# motherboard_v1_20.net
KiCad netlist of a schematic drawn in EAGLE
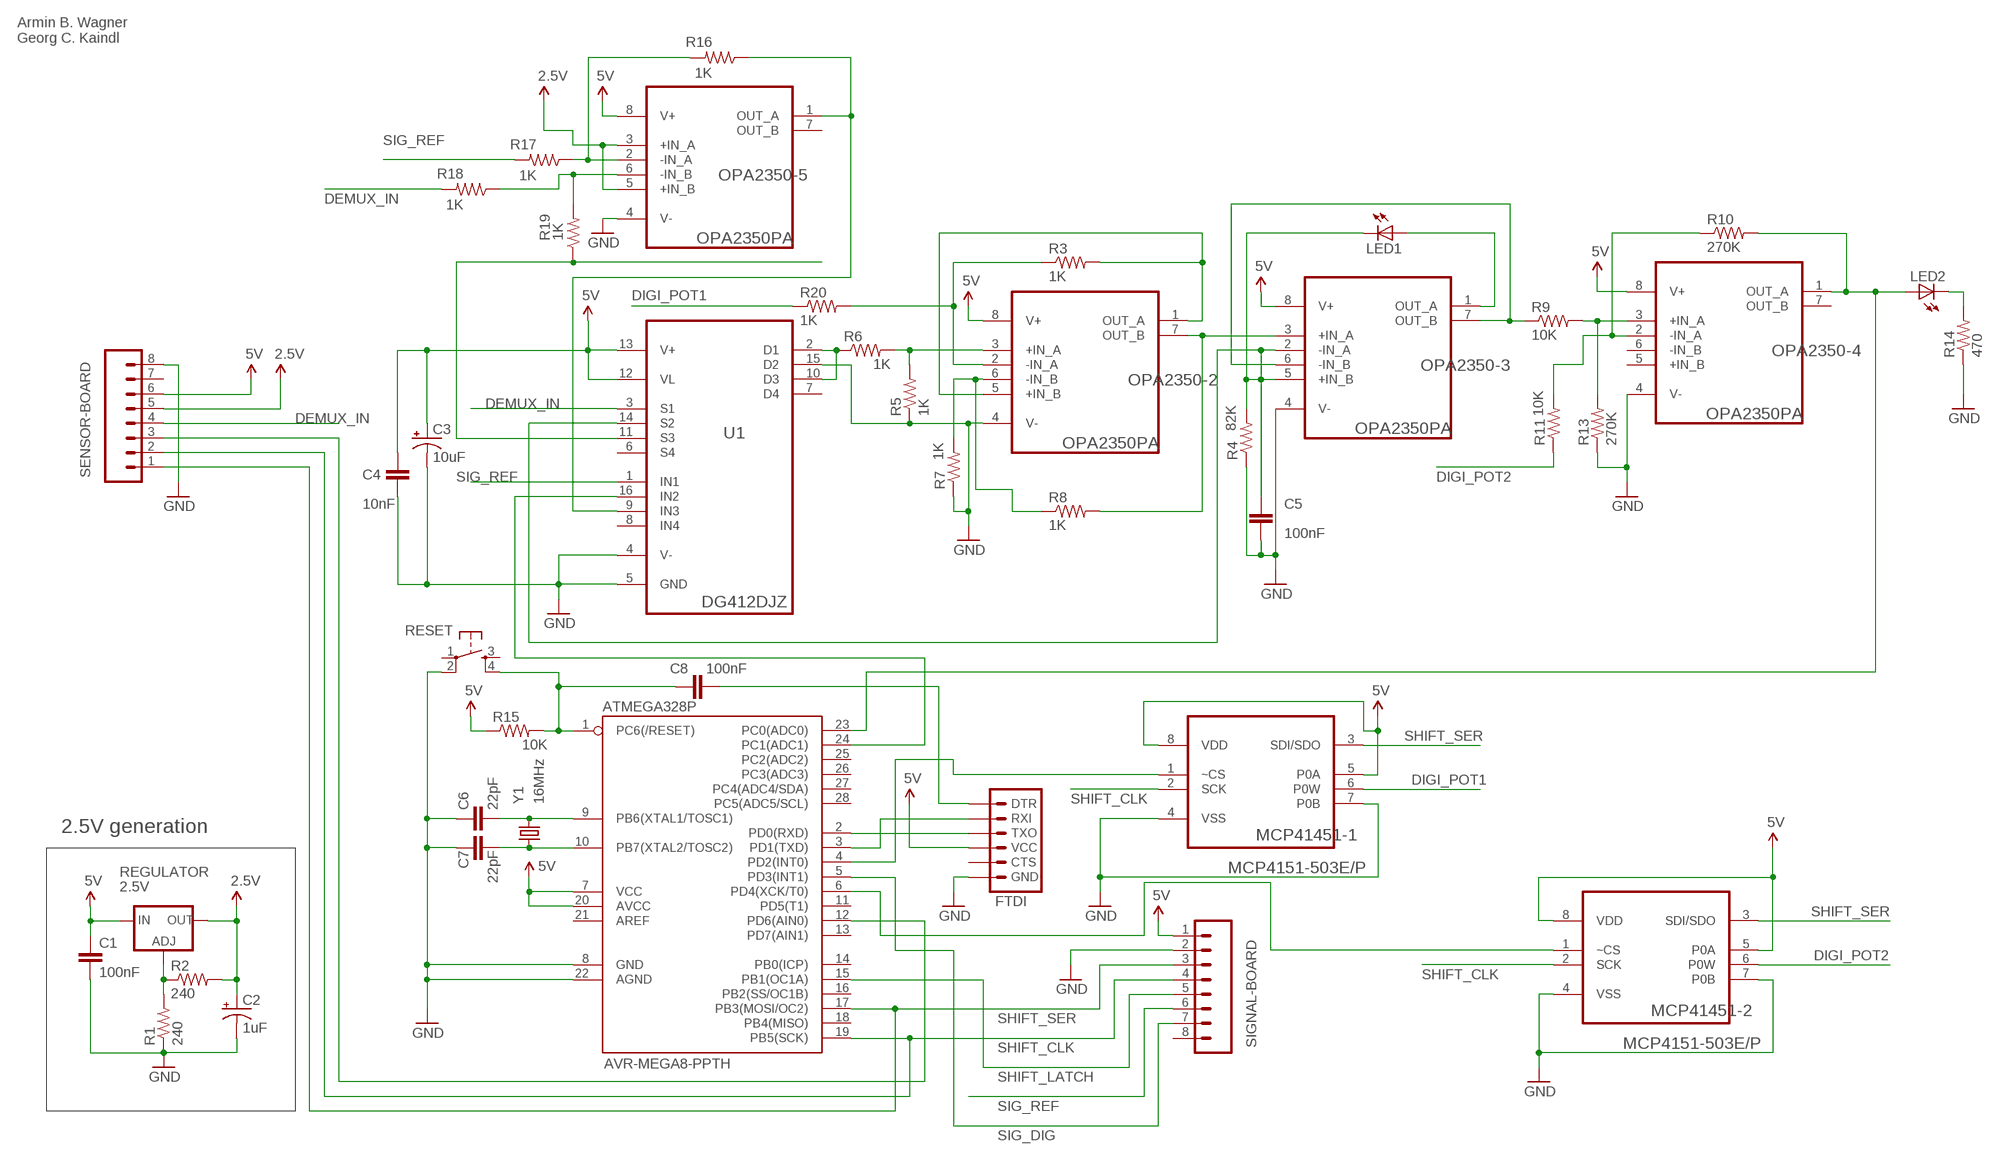
[diagram p0: schematic, sheet 1]

(export (version "E")
  (design (tool "Eeschema 10.0.6"))
  (components
    (comp (ref "ATMEGA328P")
      (value "AVR-MEGA8-PPTH")
      (footprint "eagle-import:DIL28-3")
      (libsource (lib "eagle-import") (part "AVR-MEGA8-PPTH"))
    )
    (comp (ref "C1")
      (value "100nF")
      (footprint "eagle-import:CAP-PTH-SMALL")
      (libsource (lib "eagle-import") (part "CAPPTH"))
    )
    (comp (ref "C2")
      (value "1uF")
      (footprint "eagle-import:CPOL-RADIAL-10UF-25V")
      (libsource (lib "eagle-import") (part "CAP_POLPTH2"))
    )
    (comp (ref "C3")
      (value "10uF")
      (footprint "eagle-import:CPOL-RADIAL-10UF-25V")
      (libsource (lib "eagle-import") (part "CAP_POLPTH2"))
    )
    (comp (ref "C4")
      (value "10nF")
      (footprint "eagle-import:CAP-PTH-SMALL")
      (libsource (lib "eagle-import") (part "CAPPTH"))
    )
    (comp (ref "C5")
      (value "100nF")
      (footprint "eagle-import:CAP-PTH-SMALL")
      (libsource (lib "eagle-import") (part "CAPPTH"))
    )
    (comp (ref "C6")
      (value "22pF")
      (footprint "eagle-import:CAP-PTH-SMALL2")
      (libsource (lib "eagle-import") (part "CAPPTH2"))
    )
    (comp (ref "C7")
      (value "22pF")
      (footprint "eagle-import:CAP-PTH-SMALL2")
      (libsource (lib "eagle-import") (part "CAPPTH2"))
    )
    (comp (ref "C8")
      (value "100nF")
      (footprint "eagle-import:CAP-PTH-SMALL2")
      (libsource (lib "eagle-import") (part "CAPPTH2"))
    )
    (comp (ref "FTDI")
      (value "ARDUINO_SERIAL_PROGRAMLONGPADS")
      (footprint "eagle-import:1X06_LONGPADS")
      (libsource (lib "eagle-import") (part "ARDUINO_SERIAL_PROGRAMLONGPADS"))
    )
    (comp (ref "LED1")
      (value "LED3MM")
      (footprint "eagle-import:LED3MM")
      (libsource (lib "eagle-import") (part "LED3MM"))
    )
    (comp (ref "LED2")
      (value "LED5MM")
      (footprint "eagle-import:LED5MM")
      (libsource (lib "eagle-import") (part "LED5MM"))
    )
    (comp (ref "MCP41451-1")
      (value "MCP4151-503E/P")
      (footprint "eagle-import:DIP254P762X533-8")
      (libsource (lib "eagle-import") (part "MCP4151-503E/P"))
    )
    (comp (ref "MCP41451-2")
      (value "MCP4151-503E/P")
      (footprint "eagle-import:DIP254P762X533-8")
      (libsource (lib "eagle-import") (part "MCP4151-503E/P"))
    )
    (comp (ref "OPA2350-2")
      (value "OPA2350PA")
      (footprint "eagle-import:DIP254P762X508-8")
      (libsource (lib "eagle-import") (part "OPA2350PA"))
    )
    (comp (ref "OPA2350-3")
      (value "OPA2350PA")
      (footprint "eagle-import:DIP254P762X508-8")
      (libsource (lib "eagle-import") (part "OPA2350PA"))
    )
    (comp (ref "OPA2350-4")
      (value "OPA2350PA")
      (footprint "eagle-import:DIP254P762X508-8")
      (libsource (lib "eagle-import") (part "OPA2350PA"))
    )
    (comp (ref "OPA2350-5")
      (value "OPA2350PA")
      (footprint "eagle-import:DIP254P762X508-8")
      (libsource (lib "eagle-import") (part "OPA2350PA"))
    )
    (comp (ref "R1")
      (value "240")
      (footprint "eagle-import:AXIAL-0.3")
      (libsource (lib "eagle-import") (part "RESISTORAXIAL-0.3"))
    )
    (comp (ref "R2")
      (value "240")
      (footprint "eagle-import:AXIAL-0.3")
      (libsource (lib "eagle-import") (part "RESISTORAXIAL-0.3"))
    )
    (comp (ref "R3")
      (value "1K")
      (footprint "eagle-import:AXIAL-0.3")
      (libsource (lib "eagle-import") (part "RESISTORAXIAL-0.3"))
    )
    (comp (ref "R4")
      (value "82K")
      (footprint "eagle-import:AXIAL-0.3")
      (libsource (lib "eagle-import") (part "RESISTORAXIAL-0.3"))
    )
    (comp (ref "R5")
      (value "1K")
      (footprint "eagle-import:AXIAL-0.3")
      (libsource (lib "eagle-import") (part "RESISTORAXIAL-0.3"))
    )
    (comp (ref "R6")
      (value "1K")
      (footprint "eagle-import:AXIAL-0.3")
      (libsource (lib "eagle-import") (part "RESISTORAXIAL-0.3"))
    )
    (comp (ref "R7")
      (value "1K")
      (footprint "eagle-import:AXIAL-0.3")
      (libsource (lib "eagle-import") (part "RESISTORAXIAL-0.3"))
    )
    (comp (ref "R8")
      (value "1K")
      (footprint "eagle-import:AXIAL-0.3")
      (libsource (lib "eagle-import") (part "RESISTORAXIAL-0.3"))
    )
    (comp (ref "R9")
      (value "10K")
      (footprint "eagle-import:AXIAL-0.3")
      (libsource (lib "eagle-import") (part "RESISTORAXIAL-0.3"))
    )
    (comp (ref "R10")
      (value "270K")
      (footprint "eagle-import:AXIAL-0.3")
      (libsource (lib "eagle-import") (part "RESISTORAXIAL-0.3"))
    )
    (comp (ref "R11")
      (value "10K")
      (footprint "eagle-import:AXIAL-0.3")
      (libsource (lib "eagle-import") (part "RESISTORAXIAL-0.3"))
    )
    (comp (ref "R13")
      (value "270K")
      (footprint "eagle-import:AXIAL-0.3")
      (libsource (lib "eagle-import") (part "RESISTORAXIAL-0.3"))
    )
    (comp (ref "R14")
      (value "470")
      (footprint "eagle-import:AXIAL-0.3")
      (libsource (lib "eagle-import") (part "RESISTORAXIAL-0.3"))
    )
    (comp (ref "R15")
      (value "10K")
      (footprint "eagle-import:AXIAL-0.3")
      (libsource (lib "eagle-import") (part "RESISTORAXIAL-0.3"))
    )
    (comp (ref "R16")
      (value "1K")
      (footprint "eagle-import:AXIAL-0.3")
      (libsource (lib "eagle-import") (part "RESISTORAXIAL-0.3"))
    )
    (comp (ref "R17")
      (value "1K")
      (footprint "eagle-import:AXIAL-0.3")
      (libsource (lib "eagle-import") (part "RESISTORAXIAL-0.3"))
    )
    (comp (ref "R18")
      (value "1K")
      (footprint "eagle-import:AXIAL-0.3")
      (libsource (lib "eagle-import") (part "RESISTORAXIAL-0.3"))
    )
    (comp (ref "R19")
      (value "1K")
      (footprint "eagle-import:AXIAL-0.3")
      (libsource (lib "eagle-import") (part "RESISTORAXIAL-0.3"))
    )
    (comp (ref "R20")
      (value "1K")
      (footprint "eagle-import:AXIAL-0.3")
      (libsource (lib "eagle-import") (part "RESISTORAXIAL-0.3"))
    )
    (comp (ref "REGULATOR")
      (value "2.5V")
      (footprint "eagle-import:TO220-ADJ")
      (libsource (lib "eagle-import") (part "V_REG_317SINK"))
    )
    (comp (ref "RESET")
      (value "TAC_SWITCHPTH")
      (footprint "eagle-import:TACTILE-PTH")
      (libsource (lib "eagle-import") (part "TAC_SWITCHPTH"))
    )
    (comp (ref "SENSOR-BOARD")
      (value "M08LONGPADS")
      (footprint "eagle-import:1X08_LONGPADS")
      (libsource (lib "eagle-import") (part "M08LONGPADS"))
    )
    (comp (ref "SIGNAL-BOARD")
      (value "M08LONGPADS")
      (footprint "eagle-import:1X08_LONGPADS")
      (libsource (lib "eagle-import") (part "M08LONGPADS"))
    )
    (comp (ref "U1")
      (value "DG412DJZ")
      (footprint "eagle-import:DIP254P762X533-16")
      (libsource (lib "eagle-import") (part "DG412DJZ"))
    )
    (comp (ref "Y1")
      (value "16MHz")
      (footprint "eagle-import:HC49US")
      (libsource (lib "eagle-import") (part "CRYSTALHC49US"))
    )
  )
  (nets
    (net (code "1") (name "/DEMUX_IN") (class "Default")
      (node (ref "R18") (pin "P$2") (pinfunction "2_P$2") (pintype "passive"))
      (node (ref "SENSOR-BOARD") (pin "4") (pinfunction "4_4") (pintype "passive"))
      (node (ref "U1") (pin "3") (pinfunction "S1_3") (pintype "input"))
    )
    (net (code "2") (name "/DIGI_POT1") (class "Default")
      (node (ref "MCP41451-1") (pin "6") (pinfunction "P0W_6") (pintype "passive"))
      (node (ref "R20") (pin "P$1") (pinfunction "1_P$1") (pintype "passive"))
    )
    (net (code "3") (name "/DIGI_POT2") (class "Default")
      (node (ref "MCP41451-2") (pin "6") (pinfunction "P0W_6") (pintype "passive"))
      (node (ref "R11") (pin "P$1") (pinfunction "1_P$1") (pintype "passive"))
    )
    (net (code "4") (name "/SHIFT_CLK") (class "Default")
      (node (ref "ATMEGA328P") (pin "19") (pinfunction "PB5(SCK)_19") (pintype "bidirectional"))
      (node (ref "MCP41451-1") (pin "2") (pinfunction "SCK_2") (pintype "input"))
      (node (ref "MCP41451-2") (pin "2") (pinfunction "SCK_2") (pintype "input"))
      (node (ref "SENSOR-BOARD") (pin "2") (pinfunction "2_2") (pintype "passive"))
      (node (ref "SIGNAL-BOARD") (pin "4") (pinfunction "4_4") (pintype "passive"))
    )
    (net (code "5") (name "/SHIFT_LATCH") (class "Default")
      (node (ref "ATMEGA328P") (pin "15") (pinfunction "PB1(OC1A)_15") (pintype "bidirectional"))
      (node (ref "SIGNAL-BOARD") (pin "5") (pinfunction "5_5") (pintype "passive"))
    )
    (net (code "6") (name "/SHIFT_SER") (class "Default")
      (node (ref "ATMEGA328P") (pin "17") (pinfunction "PB3(MOSI/OC2)_17") (pintype "bidirectional"))
      (node (ref "MCP41451-1") (pin "3") (pinfunction "SDI/SDO_3") (pintype "bidirectional"))
      (node (ref "MCP41451-2") (pin "3") (pinfunction "SDI/SDO_3") (pintype "bidirectional"))
      (node (ref "SENSOR-BOARD") (pin "1") (pinfunction "1_1") (pintype "passive"))
      (node (ref "SIGNAL-BOARD") (pin "3") (pinfunction "3_3") (pintype "passive"))
    )
    (net (code "7") (name "/SIG_DIG") (class "Default")
      (node (ref "ATMEGA328P") (pin "5") (pinfunction "PD3(INT1)_5") (pintype "bidirectional"))
      (node (ref "SIGNAL-BOARD") (pin "7") (pinfunction "7_7") (pintype "passive"))
    )
    (net (code "8") (name "/SIG_REF") (class "Default")
      (node (ref "R17") (pin "P$2") (pinfunction "2_P$2") (pintype "passive"))
      (node (ref "SIGNAL-BOARD") (pin "6") (pinfunction "6_6") (pintype "passive"))
      (node (ref "U1") (pin "1") (pinfunction "IN1_1") (pintype "input"))
    )
    (net (code "9") (name "2.5V") (class "Default")
      (node (ref "C2") (pin "1") (pinfunction "+_1") (pintype "passive"))
      (node (ref "OPA2350-5") (pin "3") (pinfunction "+IN_A_3") (pintype "input"))
      (node (ref "OPA2350-5") (pin "5") (pinfunction "+IN_B_5") (pintype "input"))
      (node (ref "R2") (pin "P$2") (pinfunction "2_P$2") (pintype "passive"))
      (node (ref "REGULATOR") (pin "OUT") (pinfunction "OUT_OUT") (pintype "output"))
      (node (ref "SENSOR-BOARD") (pin "5") (pinfunction "5_5") (pintype "passive"))
    )
    (net (code "10") (name "5V") (class "Default")
      (node (ref "ATMEGA328P") (pin "20") (pinfunction "AVCC_20") (pintype "bidirectional"))
      (node (ref "ATMEGA328P") (pin "7") (pinfunction "VCC_7") (pintype "bidirectional"))
      (node (ref "C1") (pin "1") (pinfunction "1_1") (pintype "passive"))
      (node (ref "C3") (pin "1") (pinfunction "+_1") (pintype "passive"))
      (node (ref "C4") (pin "1") (pinfunction "1_1") (pintype "passive"))
      (node (ref "FTDI") (pin "4") (pinfunction "VCC_4") (pintype "passive"))
      (node (ref "MCP41451-1") (pin "5") (pinfunction "P0A_5") (pintype "passive"))
      (node (ref "MCP41451-1") (pin "8") (pinfunction "VDD_8") (pintype "power_in"))
      (node (ref "MCP41451-2") (pin "5") (pinfunction "P0A_5") (pintype "passive"))
      (node (ref "MCP41451-2") (pin "8") (pinfunction "VDD_8") (pintype "power_in"))
      (node (ref "OPA2350-2") (pin "8") (pinfunction "V+_8") (pintype "power_in"))
      (node (ref "OPA2350-3") (pin "8") (pinfunction "V+_8") (pintype "power_in"))
      (node (ref "OPA2350-4") (pin "8") (pinfunction "V+_8") (pintype "power_in"))
      (node (ref "OPA2350-5") (pin "8") (pinfunction "V+_8") (pintype "power_in"))
      (node (ref "R15") (pin "P$1") (pinfunction "1_P$1") (pintype "passive"))
      (node (ref "REGULATOR") (pin "IN") (pinfunction "IN_IN") (pintype "input"))
      (node (ref "SENSOR-BOARD") (pin "6") (pinfunction "6_6") (pintype "passive"))
      (node (ref "SIGNAL-BOARD") (pin "1") (pinfunction "1_1") (pintype "passive"))
      (node (ref "U1") (pin "12") (pinfunction "VL_12") (pintype "power_in"))
      (node (ref "U1") (pin "13") (pinfunction "V+_13") (pintype "power_in"))
    )
    (net (code "11") (name "GND") (class "Default")
      (node (ref "ATMEGA328P") (pin "22") (pinfunction "AGND_22") (pintype "bidirectional"))
      (node (ref "ATMEGA328P") (pin "8") (pinfunction "GND_8") (pintype "bidirectional"))
      (node (ref "C1") (pin "2") (pinfunction "2_2") (pintype "passive"))
      (node (ref "C2") (pin "2") (pinfunction "-_2") (pintype "passive"))
      (node (ref "C3") (pin "2") (pinfunction "-_2") (pintype "passive"))
      (node (ref "C4") (pin "2") (pinfunction "2_2") (pintype "passive"))
      (node (ref "C5") (pin "2") (pinfunction "2_2") (pintype "passive"))
      (node (ref "C6") (pin "1") (pinfunction "1_1") (pintype "passive"))
      (node (ref "C7") (pin "1") (pinfunction "1_1") (pintype "passive"))
      (node (ref "FTDI") (pin "6") (pinfunction "GND_6") (pintype "passive"))
      (node (ref "MCP41451-1") (pin "4") (pinfunction "VSS_4") (pintype "power_in"))
      (node (ref "MCP41451-1") (pin "7") (pinfunction "P0B_7") (pintype "passive"))
      (node (ref "MCP41451-2") (pin "4") (pinfunction "VSS_4") (pintype "power_in"))
      (node (ref "MCP41451-2") (pin "7") (pinfunction "P0B_7") (pintype "passive"))
      (node (ref "OPA2350-2") (pin "4") (pinfunction "V-_4") (pintype "power_in"))
      (node (ref "OPA2350-3") (pin "4") (pinfunction "V-_4") (pintype "power_in"))
      (node (ref "OPA2350-4") (pin "4") (pinfunction "V-_4") (pintype "power_in"))
      (node (ref "OPA2350-5") (pin "4") (pinfunction "V-_4") (pintype "power_in"))
      (node (ref "R1") (pin "P$1") (pinfunction "1_P$1") (pintype "passive"))
      (node (ref "R13") (pin "P$1") (pinfunction "1_P$1") (pintype "passive"))
      (node (ref "R14") (pin "P$1") (pinfunction "1_P$1") (pintype "passive"))
      (node (ref "R4") (pin "P$1") (pinfunction "1_P$1") (pintype "passive"))
      (node (ref "R5") (pin "P$1") (pinfunction "1_P$1") (pintype "passive"))
      (node (ref "R7") (pin "P$1") (pinfunction "1_P$1") (pintype "passive"))
      (node (ref "RESET") (pin "2") (pinfunction "2_2") (pintype "passive"))
      (node (ref "SENSOR-BOARD") (pin "8") (pinfunction "8_8") (pintype "passive"))
      (node (ref "SIGNAL-BOARD") (pin "2") (pinfunction "2_2") (pintype "passive"))
      (node (ref "U1") (pin "15") (pinfunction "D2_15") (pintype "output"))
      (node (ref "U1") (pin "4") (pinfunction "V-_4") (pintype "power_in"))
      (node (ref "U1") (pin "5") (pinfunction "GND_5") (pintype "passive"))
    )
    (net (code "12") (name "Net-(ATMEGA328P-PB6(XTAL1{slash}TOSC1))") (class "Default")
      (node (ref "ATMEGA328P") (pin "9") (pinfunction "PB6(XTAL1/TOSC1)_9") (pintype "bidirectional"))
      (node (ref "C6") (pin "2") (pinfunction "2_2") (pintype "passive"))
      (node (ref "Y1") (pin "2") (pinfunction "2_2") (pintype "passive"))
    )
    (net (code "13") (name "Net-(ATMEGA328P-PB7(XTAL2{slash}TOSC2))") (class "Default")
      (node (ref "ATMEGA328P") (pin "10") (pinfunction "PB7(XTAL2/TOSC2)_10") (pintype "bidirectional"))
      (node (ref "C7") (pin "2") (pinfunction "2_2") (pintype "passive"))
      (node (ref "Y1") (pin "1") (pinfunction "1_1") (pintype "passive"))
    )
    (net (code "14") (name "Net-(ATMEGA328P-PC0(ADC0))") (class "Default")
      (node (ref "ATMEGA328P") (pin "23") (pinfunction "PC0(ADC0)_23") (pintype "bidirectional"))
      (node (ref "LED2") (pin "A") (pinfunction "A_A") (pintype "passive"))
      (node (ref "OPA2350-4") (pin "1") (pinfunction "OUT_A_1") (pintype "output"))
      (node (ref "R10") (pin "P$2") (pinfunction "2_P$2") (pintype "passive"))
    )
    (net (code "15") (name "Net-(ATMEGA328P-PC1(ADC1))") (class "Default")
      (node (ref "ATMEGA328P") (pin "24") (pinfunction "PC1(ADC1)_24") (pintype "bidirectional"))
      (node (ref "U1") (pin "16") (pinfunction "IN2_16") (pintype "input"))
    )
    (net (code "16") (name "Net-(ATMEGA328P-PC6({slash}RESET))") (class "Default")
      (node (ref "ATMEGA328P") (pin "1") (pinfunction "PC6(/RESET)_1") (pintype "bidirectional"))
      (node (ref "C8") (pin "1") (pinfunction "1_1") (pintype "passive"))
      (node (ref "R15") (pin "P$2") (pinfunction "2_P$2") (pintype "passive"))
      (node (ref "RESET") (pin "4") (pinfunction "4_4") (pintype "passive"))
    )
    (net (code "17") (name "Net-(ATMEGA328P-PD0(RXD))") (class "Default")
      (node (ref "ATMEGA328P") (pin "2") (pinfunction "PD0(RXD)_2") (pintype "bidirectional"))
      (node (ref "FTDI") (pin "3") (pinfunction "TXO_3") (pintype "passive"))
    )
    (net (code "18") (name "Net-(ATMEGA328P-PD1(TXD))") (class "Default")
      (node (ref "ATMEGA328P") (pin "3") (pinfunction "PD1(TXD)_3") (pintype "bidirectional"))
      (node (ref "FTDI") (pin "2") (pinfunction "RXI_2") (pintype "passive"))
    )
    (net (code "19") (name "Net-(ATMEGA328P-PD2(INT0))") (class "Default")
      (node (ref "ATMEGA328P") (pin "4") (pinfunction "PD2(INT0)_4") (pintype "bidirectional"))
      (node (ref "MCP41451-1") (pin "1") (pinfunction "~{CS}_1") (pintype "input"))
    )
    (net (code "20") (name "Net-(ATMEGA328P-PD4(XCK{slash}T0))") (class "Default")
      (node (ref "ATMEGA328P") (pin "6") (pinfunction "PD4(XCK/T0)_6") (pintype "bidirectional"))
      (node (ref "MCP41451-2") (pin "1") (pinfunction "~{CS}_1") (pintype "input"))
    )
    (net (code "21") (name "Net-(ATMEGA328P-PD6(AIN0))") (class "Default")
      (node (ref "ATMEGA328P") (pin "12") (pinfunction "PD6(AIN0)_12") (pintype "bidirectional"))
      (node (ref "SENSOR-BOARD") (pin "3") (pinfunction "3_3") (pintype "passive"))
    )
    (net (code "22") (name "Net-(FTDI-DTR)") (class "Default")
      (node (ref "C8") (pin "2") (pinfunction "2_2") (pintype "passive"))
      (node (ref "FTDI") (pin "1") (pinfunction "DTR_1") (pintype "passive"))
    )
    (net (code "23") (name "Net-(LED1-C)") (class "Default")
      (node (ref "C5") (pin "1") (pinfunction "1_1") (pintype "passive"))
      (node (ref "LED1") (pin "K") (pinfunction "C_K") (pintype "passive"))
      (node (ref "OPA2350-3") (pin "2") (pinfunction "-IN_A_2") (pintype "input"))
      (node (ref "OPA2350-3") (pin "5") (pinfunction "+IN_B_5") (pintype "input"))
      (node (ref "R4") (pin "P$2") (pinfunction "2_P$2") (pintype "passive"))
      (node (ref "U1") (pin "14") (pinfunction "S2_14") (pintype "input"))
    )
    (net (code "24") (name "Net-(LED2-C)") (class "Default")
      (node (ref "LED2") (pin "K") (pinfunction "C_K") (pintype "passive"))
      (node (ref "R14") (pin "P$2") (pinfunction "2_P$2") (pintype "passive"))
    )
    (net (code "25") (name "Net-(OPA2350-2-+IN_A)") (class "Default")
      (node (ref "OPA2350-2") (pin "3") (pinfunction "+IN_A_3") (pintype "input"))
      (node (ref "R5") (pin "P$2") (pinfunction "2_P$2") (pintype "passive"))
      (node (ref "R6") (pin "P$2") (pinfunction "2_P$2") (pintype "passive"))
    )
    (net (code "26") (name "Net-(OPA2350-2-+IN_B)") (class "Default")
      (node (ref "OPA2350-2") (pin "1") (pinfunction "OUT_A_1") (pintype "output"))
      (node (ref "OPA2350-2") (pin "5") (pinfunction "+IN_B_5") (pintype "input"))
      (node (ref "R3") (pin "P$2") (pinfunction "2_P$2") (pintype "passive"))
    )
    (net (code "27") (name "Net-(OPA2350-2--IN_A)") (class "Default")
      (node (ref "OPA2350-2") (pin "2") (pinfunction "-IN_A_2") (pintype "input"))
      (node (ref "R20") (pin "P$2") (pinfunction "2_P$2") (pintype "passive"))
      (node (ref "R3") (pin "P$1") (pinfunction "1_P$1") (pintype "passive"))
    )
    (net (code "28") (name "Net-(OPA2350-2--IN_B)") (class "Default")
      (node (ref "OPA2350-2") (pin "6") (pinfunction "-IN_B_6") (pintype "input"))
      (node (ref "R7") (pin "P$2") (pinfunction "2_P$2") (pintype "passive"))
      (node (ref "R8") (pin "P$1") (pinfunction "1_P$1") (pintype "passive"))
    )
    (net (code "29") (name "Net-(OPA2350-2-OUT_B)") (class "Default")
      (node (ref "OPA2350-2") (pin "7") (pinfunction "OUT_B_7") (pintype "output"))
      (node (ref "OPA2350-3") (pin "3") (pinfunction "+IN_A_3") (pintype "input"))
      (node (ref "R8") (pin "P$2") (pinfunction "2_P$2") (pintype "passive"))
    )
    (net (code "30") (name "Net-(OPA2350-3--IN_B)") (class "Default")
      (node (ref "OPA2350-3") (pin "6") (pinfunction "-IN_B_6") (pintype "input"))
      (node (ref "OPA2350-3") (pin "7") (pinfunction "OUT_B_7") (pintype "output"))
      (node (ref "R9") (pin "P$1") (pinfunction "1_P$1") (pintype "passive"))
    )
    (net (code "31") (name "Net-(OPA2350-3-OUT_A)") (class "Default")
      (node (ref "LED1") (pin "A") (pinfunction "A_A") (pintype "passive"))
      (node (ref "OPA2350-3") (pin "1") (pinfunction "OUT_A_1") (pintype "output"))
    )
    (net (code "32") (name "Net-(OPA2350-4-+IN_A)") (class "Default")
      (node (ref "OPA2350-4") (pin "3") (pinfunction "+IN_A_3") (pintype "input"))
      (node (ref "R13") (pin "P$2") (pinfunction "2_P$2") (pintype "passive"))
      (node (ref "R9") (pin "P$2") (pinfunction "2_P$2") (pintype "passive"))
    )
    (net (code "33") (name "Net-(OPA2350-4--IN_A)") (class "Default")
      (node (ref "OPA2350-4") (pin "2") (pinfunction "-IN_A_2") (pintype "input"))
      (node (ref "R10") (pin "P$1") (pinfunction "1_P$1") (pintype "passive"))
      (node (ref "R11") (pin "P$2") (pinfunction "2_P$2") (pintype "passive"))
    )
    (net (code "34") (name "Net-(OPA2350-5--IN_A)") (class "Default")
      (node (ref "OPA2350-5") (pin "2") (pinfunction "-IN_A_2") (pintype "input"))
      (node (ref "R16") (pin "P$2") (pinfunction "2_P$2") (pintype "passive"))
      (node (ref "R17") (pin "P$1") (pinfunction "1_P$1") (pintype "passive"))
    )
    (net (code "35") (name "Net-(OPA2350-5--IN_B)") (class "Default")
      (node (ref "OPA2350-5") (pin "6") (pinfunction "-IN_B_6") (pintype "input"))
      (node (ref "R18") (pin "P$1") (pinfunction "1_P$1") (pintype "passive"))
      (node (ref "R19") (pin "P$2") (pinfunction "2_P$2") (pintype "passive"))
    )
    (net (code "36") (name "Net-(OPA2350-5-OUT_A)") (class "Default")
      (node (ref "OPA2350-5") (pin "1") (pinfunction "OUT_A_1") (pintype "output"))
      (node (ref "R16") (pin "P$1") (pinfunction "1_P$1") (pintype "passive"))
      (node (ref "U1") (pin "9") (pinfunction "IN3_9") (pintype "input"))
    )
    (net (code "37") (name "Net-(R1-2)") (class "Default")
      (node (ref "R1") (pin "P$2") (pinfunction "2_P$2") (pintype "passive"))
      (node (ref "R2") (pin "P$1") (pinfunction "1_P$1") (pintype "passive"))
      (node (ref "REGULATOR") (pin "ADJ") (pinfunction "ADJ_ADJ") (pintype "input"))
    )
    (net (code "38") (name "Net-(R6-1)") (class "Default")
      (node (ref "R6") (pin "P$1") (pinfunction "1_P$1") (pintype "passive"))
      (node (ref "U1") (pin "10") (pinfunction "D3_10") (pintype "output"))
      (node (ref "U1") (pin "2") (pinfunction "D1_2") (pintype "output"))
    )
    (net (code "39") (name "Net-(R19-1)") (class "Default")
      (node (ref "R19") (pin "P$1") (pinfunction "1_P$1") (pintype "passive"))
      (node (ref "U1") (pin "11") (pinfunction "S3_11") (pintype "input"))
    )
    (net (code "40") (name "unconnected-(ATMEGA328P-AREF-Pad21)") (class "Default")
      (node (ref "ATMEGA328P") (pin "21") (pinfunction "AREF_21") (pintype "bidirectional"))
    )
    (net (code "41") (name "unconnected-(ATMEGA328P-PB0(ICP)-Pad14)") (class "Default")
      (node (ref "ATMEGA328P") (pin "14") (pinfunction "PB0(ICP)_14") (pintype "bidirectional"))
    )
    (net (code "42") (name "unconnected-(ATMEGA328P-PB2(SS{slash}OC1B)-Pad16)") (class "Default")
      (node (ref "ATMEGA328P") (pin "16") (pinfunction "PB2(SS/OC1B)_16") (pintype "bidirectional"))
    )
    (net (code "43") (name "unconnected-(ATMEGA328P-PB4(MISO)-Pad18)") (class "Default")
      (node (ref "ATMEGA328P") (pin "18") (pinfunction "PB4(MISO)_18") (pintype "bidirectional"))
    )
    (net (code "44") (name "unconnected-(ATMEGA328P-PC2(ADC2)-Pad25)") (class "Default")
      (node (ref "ATMEGA328P") (pin "25") (pinfunction "PC2(ADC2)_25") (pintype "bidirectional"))
    )
    (net (code "45") (name "unconnected-(ATMEGA328P-PC3(ADC3)-Pad26)") (class "Default")
      (node (ref "ATMEGA328P") (pin "26") (pinfunction "PC3(ADC3)_26") (pintype "bidirectional"))
    )
    (net (code "46") (name "unconnected-(ATMEGA328P-PC4(ADC4{slash}SDA)-Pad27)") (class "Default")
      (node (ref "ATMEGA328P") (pin "27") (pinfunction "PC4(ADC4/SDA)_27") (pintype "bidirectional"))
    )
    (net (code "47") (name "unconnected-(ATMEGA328P-PC5(ADC5{slash}SCL)-Pad28)") (class "Default")
      (node (ref "ATMEGA328P") (pin "28") (pinfunction "PC5(ADC5/SCL)_28") (pintype "bidirectional"))
    )
    (net (code "48") (name "unconnected-(ATMEGA328P-PD5(T1)-Pad11)") (class "Default")
      (node (ref "ATMEGA328P") (pin "11") (pinfunction "PD5(T1)_11") (pintype "bidirectional"))
    )
    (net (code "49") (name "unconnected-(ATMEGA328P-PD7(AIN1)-Pad13)") (class "Default")
      (node (ref "ATMEGA328P") (pin "13") (pinfunction "PD7(AIN1)_13") (pintype "bidirectional"))
    )
    (net (code "50") (name "unconnected-(FTDI-CTS-Pad5)") (class "Default")
      (node (ref "FTDI") (pin "5") (pinfunction "CTS_5") (pintype "passive"))
    )
    (net (code "51") (name "unconnected-(OPA2350-4-+IN_B-Pad5)") (class "Default")
      (node (ref "OPA2350-4") (pin "5") (pinfunction "+IN_B_5") (pintype "input"))
    )
    (net (code "52") (name "unconnected-(OPA2350-4--IN_B-Pad6)") (class "Default")
      (node (ref "OPA2350-4") (pin "6") (pinfunction "-IN_B_6") (pintype "input"))
    )
    (net (code "53") (name "unconnected-(OPA2350-4-OUT_B-Pad7)") (class "Default")
      (node (ref "OPA2350-4") (pin "7") (pinfunction "OUT_B_7") (pintype "output"))
    )
    (net (code "54") (name "unconnected-(OPA2350-5-OUT_B-Pad7)") (class "Default")
      (node (ref "OPA2350-5") (pin "7") (pinfunction "OUT_B_7") (pintype "output"))
    )
    (net (code "55") (name "unconnected-(RESET-Pad1)") (class "Default")
      (node (ref "RESET") (pin "1") (pinfunction "1_1") (pintype "passive"))
    )
    (net (code "56") (name "unconnected-(RESET-Pad3)") (class "Default")
      (node (ref "RESET") (pin "3") (pinfunction "3_3") (pintype "passive"))
    )
    (net (code "57") (name "unconnected-(SENSOR-BOARD-Pad7)") (class "Default")
      (node (ref "SENSOR-BOARD") (pin "7") (pinfunction "7_7") (pintype "passive"))
    )
    (net (code "58") (name "unconnected-(SIGNAL-BOARD-Pad8)") (class "Default")
      (node (ref "SIGNAL-BOARD") (pin "8") (pinfunction "8_8") (pintype "passive"))
    )
    (net (code "59") (name "unconnected-(U1-D4-Pad7)") (class "Default")
      (node (ref "U1") (pin "7") (pinfunction "D4_7") (pintype "output"))
    )
    (net (code "60") (name "unconnected-(U1-IN4-Pad8)") (class "Default")
      (node (ref "U1") (pin "8") (pinfunction "IN4_8") (pintype "input"))
    )
    (net (code "61") (name "unconnected-(U1-S4-Pad6)") (class "Default")
      (node (ref "U1") (pin "6") (pinfunction "S4_6") (pintype "input"))
    )
  )
)
